# charger.net
KiCad netlist of a schematic drawn in Altium Designer
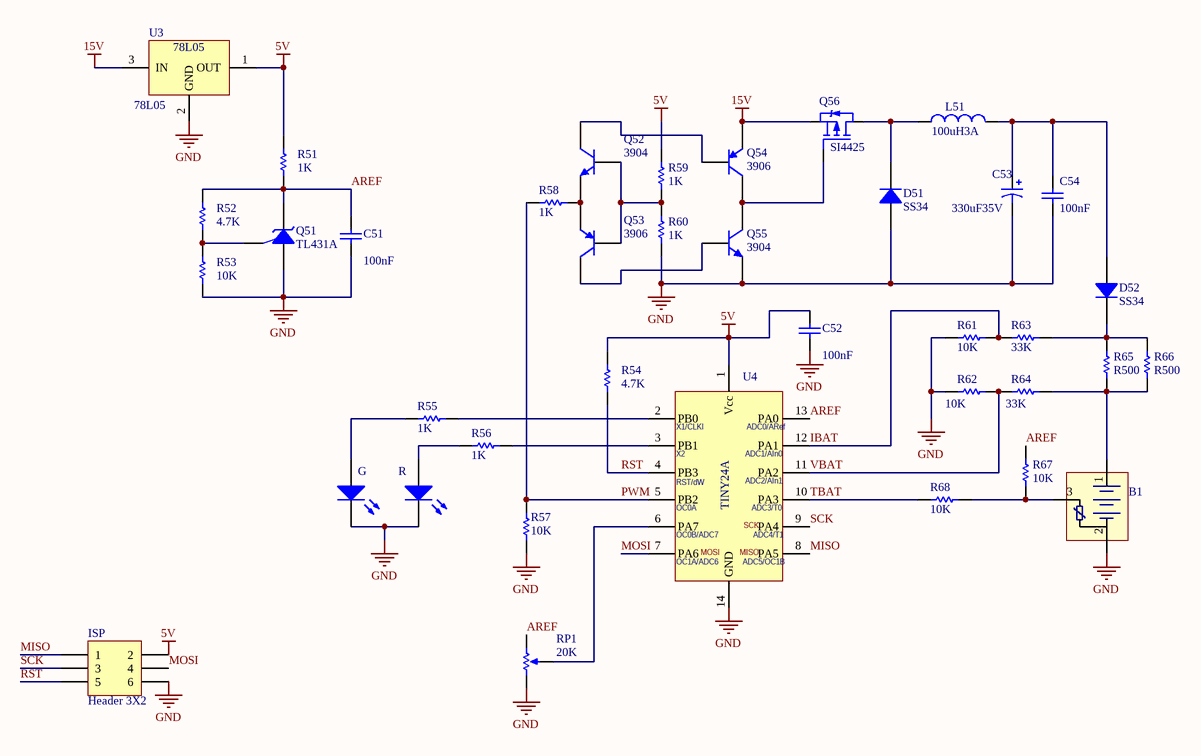
[diagram p0: charger.SchDoc]

(export (version "E")
  (design (tool "Eeschema 10.0.6"))
  (components
    (comp (ref "B1")
      (value "BATT")
      (footprint "BATT")
      (description "电池座")
      (libsource (lib "nizn") (part "BATT"))
    )
    (comp (ref "C51")
      (value "100nF")
      (footprint "CAP0805")
      (description "贴片电容")
      (fields (field (name "Comment") "Cap") (field (name "PUBLISHER") "Altium Limited"))
      (libsource (lib "Miscellaneous Devices") (part "Cap"))
    )
    (comp (ref "C52")
      (value "100nF")
      (footprint "CAP0805")
      (description "贴片电容")
      (fields (field (name "Comment") "Cap") (field (name "PUBLISHER") "Altium Limited"))
      (libsource (lib "Miscellaneous Devices") (part "Cap"))
    )
    (comp (ref "C53")
      (value "330uF35V")
      (footprint "CAP10x16")
      (description "电解电容")
      (fields (field (name "PUBLISHER") "Altium Limited"))
      (libsource (lib "nizn") (part "Cap Pol2"))
    )
    (comp (ref "C54")
      (value "100nF")
      (footprint "CAP0805")
      (description "贴片电容")
      (fields (field (name "Comment") "Cap") (field (name "PUBLISHER") "Altium Limited"))
      (libsource (lib "Miscellaneous Devices") (part "Cap"))
    )
    (comp (ref "D51")
      (value "SS34")
      (footprint "DO214A")
      (description "贴片二极管")
      (fields (field (name "PUBLISHER") "Altium Limited"))
      (libsource (lib "nizn") (part "Diode"))
    )
    (comp (ref "D52")
      (value "SS34")
      (footprint "DO214A")
      (description "贴片二极管")
      (fields (field (name "PUBLISHER") "Altium Limited"))
      (libsource (lib "nizn") (part "Diode"))
    )
    (comp (ref "G")
      (value "高亮翠绿")
      (footprint "LED2G_SLIM")
      (description "贴片二极管 0805")
      (fields (field (name "PUBLISHER") "Altium Limited"))
      (libsource (lib "magcontrol") (part "LED"))
    )
    (comp (ref "ISP")
      (value "Header 3X2")
      (footprint "HDR2X3_EMPTY")
      (description "空")
      (fields (field (name "PUBLISHER") "Altium Limited"))
      (libsource (lib "Miscellaneous Connectors") (part "Header 3X2"))
    )
    (comp (ref "L51")
      (value "100uH3A")
      (footprint "INDUCTOR")
      (description "工字电感")
      (fields (field (name "PUBLISHER") "Altium Limited"))
      (libsource (lib "nizn") (part "Inductor"))
    )
    (comp (ref "Q51")
      (value "TL431A")
      (footprint "SOT23_431")
      (description "基准集成电路")
      (fields (field (name "PUBLISHER") "Altium Limited"))
      (libsource (lib "nizn") (part "TL431"))
    )
    (comp (ref "Q52")
      (value "3904")
      (footprint "SOT23_CBE")
      (description "NPN 三极管")
      (fields (field (name "PUBLISHER") "Altium Limited"))
      (libsource (lib "nizn") (part "NPN"))
    )
    (comp (ref "Q53")
      (value "3906")
      (footprint "SOT23_CBE")
      (description "PNP 三极管")
      (fields (field (name "PUBLISHER") "Altium Limited"))
      (libsource (lib "nizn") (part "PNP"))
    )
    (comp (ref "Q54")
      (value "3906")
      (footprint "SOT23_CBE")
      (description "PNP 三极管")
      (fields (field (name "PUBLISHER") "Altium Limited"))
      (libsource (lib "nizn") (part "PNP"))
    )
    (comp (ref "Q55")
      (value "3904")
      (footprint "SOT23_CBE")
      (description "NPN 三极管")
      (fields (field (name "PUBLISHER") "Altium Limited"))
      (libsource (lib "nizn") (part "NPN"))
    )
    (comp (ref "Q56")
      (value "SI4425")
      (footprint "SO8-MOS")
      (description "低压 PMOS")
      (fields (field (name "PUBLISHER") "Altium Limited"))
      (libsource (lib "nizn") (part "PMOS"))
    )
    (comp (ref "R")
      (value "高亮红")
      (footprint "LED2R_SLIM")
      (description "贴片二极管 0805")
      (fields (field (name "PUBLISHER") "Altium Limited"))
      (libsource (lib "magcontrol") (part "LED"))
    )
    (comp (ref "R51")
      (value "1K")
      (footprint "RES0805")
      (description "贴片电阻")
      (fields (field (name "Comment") "Res1") (field (name "PUBLISHER") "Altium Limited"))
      (libsource (lib "Miscellaneous Devices") (part "Res1"))
    )
    (comp (ref "R52")
      (value "4.7K")
      (footprint "RES0805")
      (description "贴片电阻")
      (fields (field (name "Comment") "Res1") (field (name "PUBLISHER") "Altium Limited"))
      (libsource (lib "Miscellaneous Devices") (part "Res1"))
    )
    (comp (ref "R53")
      (value "10K")
      (footprint "RES0805")
      (description "贴片电阻")
      (fields (field (name "Comment") "Res1") (field (name "PUBLISHER") "Altium Limited"))
      (libsource (lib "Miscellaneous Devices") (part "Res1"))
    )
    (comp (ref "R54")
      (value "4.7K")
      (footprint "RES0805")
      (description "贴片电阻")
      (fields (field (name "Comment") "Res1") (field (name "PUBLISHER") "Altium Limited"))
      (libsource (lib "Miscellaneous Devices") (part "Res1"))
    )
    (comp (ref "R55")
      (value "1K")
      (footprint "RES0805")
      (description "贴片电阻")
      (fields (field (name "Comment") "Res1") (field (name "PUBLISHER") "Altium Limited"))
      (libsource (lib "Miscellaneous Devices") (part "Res1"))
    )
    (comp (ref "R56")
      (value "1K")
      (footprint "RES0805")
      (description "贴片电阻")
      (fields (field (name "Comment") "Res1") (field (name "PUBLISHER") "Altium Limited"))
      (libsource (lib "Miscellaneous Devices") (part "Res1"))
    )
    (comp (ref "R57")
      (value "10K")
      (footprint "RES0805")
      (description "贴片电阻")
      (fields (field (name "Comment") "Res1") (field (name "PUBLISHER") "Altium Limited"))
      (libsource (lib "Miscellaneous Devices") (part "Res1"))
    )
    (comp (ref "R58")
      (value "1K")
      (footprint "RES0805")
      (description "贴片电阻")
      (fields (field (name "Comment") "Res1") (field (name "PUBLISHER") "Altium Limited"))
      (libsource (lib "Miscellaneous Devices") (part "Res1"))
    )
    (comp (ref "R59")
      (value "1K")
      (footprint "RES0805")
      (description "贴片电阻")
      (fields (field (name "Comment") "Res1") (field (name "PUBLISHER") "Altium Limited"))
      (libsource (lib "Miscellaneous Devices") (part "Res1"))
    )
    (comp (ref "R60")
      (value "1K")
      (footprint "RES0805")
      (description "贴片电阻")
      (fields (field (name "Comment") "Res1") (field (name "PUBLISHER") "Altium Limited"))
      (libsource (lib "Miscellaneous Devices") (part "Res1"))
    )
    (comp (ref "R61")
      (value "10K")
      (footprint "RES0805")
      (description "贴片电阻")
      (fields (field (name "Comment") "Res1") (field (name "PUBLISHER") "Altium Limited"))
      (libsource (lib "Miscellaneous Devices") (part "Res1"))
    )
    (comp (ref "R62")
      (value "10K")
      (footprint "RES0805")
      (description "贴片电阻")
      (fields (field (name "Comment") "Res1") (field (name "PUBLISHER") "Altium Limited"))
      (libsource (lib "Miscellaneous Devices") (part "Res1"))
    )
    (comp (ref "R63")
      (value "33K")
      (footprint "RES0805")
      (description "贴片电阻")
      (fields (field (name "Comment") "Res1") (field (name "PUBLISHER") "Altium Limited"))
      (libsource (lib "Miscellaneous Devices") (part "Res1"))
    )
    (comp (ref "R64")
      (value "33K")
      (footprint "RES0805")
      (description "贴片电阻")
      (fields (field (name "Comment") "Res1") (field (name "PUBLISHER") "Altium Limited"))
      (libsource (lib "Miscellaneous Devices") (part "Res1"))
    )
    (comp (ref "R65")
      (value "R500")
      (footprint "RES2512")
      (description "贴片电阻")
      (fields (field (name "Comment") "Res1") (field (name "PUBLISHER") "Altium Limited"))
      (libsource (lib "Miscellaneous Devices") (part "Res1"))
    )
    (comp (ref "R66")
      (value "R500")
      (footprint "RES2512")
      (description "贴片电阻")
      (fields (field (name "Comment") "Res1") (field (name "PUBLISHER") "Altium Limited"))
      (libsource (lib "Miscellaneous Devices") (part "Res1"))
    )
    (comp (ref "R67")
      (value "10K")
      (footprint "RES0805")
      (description "贴片电阻")
      (fields (field (name "Comment") "Res1") (field (name "PUBLISHER") "Altium Limited"))
      (libsource (lib "Miscellaneous Devices") (part "Res1"))
    )
    (comp (ref "R68")
      (value "10K")
      (footprint "RES0805")
      (description "贴片电阻")
      (fields (field (name "Comment") "Res1") (field (name "PUBLISHER") "Altium Limited"))
      (libsource (lib "Miscellaneous Devices") (part "Res1"))
    )
    (comp (ref "RP1")
      (value "20K")
      (footprint "POT3x3")
      (description "贴片电位器")
      (fields (field (name "Comment") "RPot") (field (name "PUBLISHER") "Altium Limited"))
      (libsource (lib "Miscellaneous Devices") (part "RPot"))
    )
    (comp (ref "U3")
      (value "78L05")
      (footprint "SOT89_VREG")
      (description "三端稳压贴片")
      (fields (field (name "PUBLISHER") "Altium Limited"))
      (libsource (lib "magcontrol") (part "78L05"))
    )
    (comp (ref "U4")
      (value "TINY24A")
      (footprint "SO14")
      (description "集成电路")
      (libsource (lib "nizn") (part "TINY13A"))
    )
  )
  (nets
    (net (code "1") (name "/AREF") (class "Default")
      (node (ref "C51") (pin "2") (pinfunction "2_2") (pintype "passive"))
      (node (ref "Q51") (pin "3") (pinfunction "C_3") (pintype "passive"))
      (node (ref "R51") (pin "1") (pinfunction "1_1") (pintype "passive"))
      (node (ref "R52") (pin "2") (pinfunction "2_2") (pintype "passive"))
      (node (ref "R67") (pin "2") (pinfunction "2_2") (pintype "passive"))
      (node (ref "RP1") (pin "2") (pinfunction "BOT_2") (pintype "passive"))
      (node (ref "U4") (pin "13") (pinfunction "PA0_13") (pintype "power_in"))
    )
    (net (code "2") (name "/IBAT") (class "Default")
      (node (ref "R61") (pin "1") (pinfunction "1_1") (pintype "passive"))
      (node (ref "R63") (pin "2") (pinfunction "2_2") (pintype "passive"))
      (node (ref "U4") (pin "12") (pinfunction "PA1_12") (pintype "power_in"))
    )
    (net (code "3") (name "/MISO") (class "Default")
      (node (ref "ISP") (pin "1") (pinfunction "1_1") (pintype "passive"))
      (node (ref "U4") (pin "8") (pinfunction "PA5_8") (pintype "power_in"))
    )
    (net (code "4") (name "/MOSI") (class "Default")
      (node (ref "ISP") (pin "4") (pinfunction "4_4") (pintype "passive"))
      (node (ref "U4") (pin "7") (pinfunction "PA6_7") (pintype "power_in"))
    )
    (net (code "5") (name "/PWM") (class "Default")
      (node (ref "R57") (pin "1") (pinfunction "1_1") (pintype "passive"))
      (node (ref "R58") (pin "2") (pinfunction "2_2") (pintype "passive"))
      (node (ref "U4") (pin "5") (pinfunction "PB2_5") (pintype "power_in"))
    )
    (net (code "6") (name "/RST") (class "Default")
      (node (ref "ISP") (pin "5") (pinfunction "5_5") (pintype "passive"))
      (node (ref "R54") (pin "1") (pinfunction "1_1") (pintype "passive"))
      (node (ref "U4") (pin "4") (pinfunction "PB3_4") (pintype "power_in"))
    )
    (net (code "7") (name "/SCK") (class "Default")
      (node (ref "ISP") (pin "3") (pinfunction "3_3") (pintype "passive"))
      (node (ref "U4") (pin "9") (pinfunction "PA4_9") (pintype "power_in"))
    )
    (net (code "8") (name "/TBAT") (class "Default")
      (node (ref "R68") (pin "2") (pinfunction "2_2") (pintype "passive"))
      (node (ref "U4") (pin "10") (pinfunction "PA3_10") (pintype "power_in"))
    )
    (net (code "9") (name "/VBAT") (class "Default")
      (node (ref "R62") (pin "1") (pinfunction "1_1") (pintype "passive"))
      (node (ref "R64") (pin "2") (pinfunction "2_2") (pintype "passive"))
      (node (ref "U4") (pin "11") (pinfunction "PA2_11") (pintype "power_in"))
    )
    (net (code "10") (name "5V") (class "Default")
      (node (ref "C52") (pin "2") (pinfunction "2_2") (pintype "passive"))
      (node (ref "ISP") (pin "2") (pinfunction "2_2") (pintype "passive"))
      (node (ref "R51") (pin "2") (pinfunction "2_2") (pintype "passive"))
      (node (ref "R54") (pin "2") (pinfunction "2_2") (pintype "passive"))
      (node (ref "R59") (pin "2") (pinfunction "2_2") (pintype "passive"))
      (node (ref "U3") (pin "1") (pinfunction "OUT_1") (pintype "power_in"))
      (node (ref "U4") (pin "1") (pinfunction "Vcc_1") (pintype "power_in"))
    )
    (net (code "11") (name "15V") (class "Default")
      (node (ref "Q54") (pin "E") (pinfunction "E_E") (pintype "passive"))
      (node (ref "Q56") (pin "S") (pinfunction "S_S") (pintype "passive"))
      (node (ref "U3") (pin "3") (pinfunction "IN_3") (pintype "power_in"))
    )
    (net (code "12") (name "GND") (class "Default")
      (node (ref "B1") (pin "2") (pinfunction "B-_2") (pintype "power_in"))
      (node (ref "C51") (pin "1") (pinfunction "1_1") (pintype "passive"))
      (node (ref "C52") (pin "1") (pinfunction "1_1") (pintype "passive"))
      (node (ref "C53") (pin "2") (pinfunction "2_2") (pintype "passive"))
      (node (ref "C54") (pin "1") (pinfunction "1_1") (pintype "passive"))
      (node (ref "D51") (pin "1") (pinfunction "A_1") (pintype "passive"))
      (node (ref "G") (pin "2") (pinfunction "K_2") (pintype "passive"))
      (node (ref "ISP") (pin "6") (pinfunction "6_6") (pintype "passive"))
      (node (ref "Q51") (pin "2") (pinfunction "A_2") (pintype "passive"))
      (node (ref "Q55") (pin "E") (pinfunction "E_E") (pintype "passive"))
      (node (ref "R") (pin "2") (pinfunction "K_2") (pintype "passive"))
      (node (ref "R53") (pin "1") (pinfunction "1_1") (pintype "passive"))
      (node (ref "R57") (pin "2") (pinfunction "2_2") (pintype "passive"))
      (node (ref "R60") (pin "1") (pinfunction "1_1") (pintype "passive"))
      (node (ref "R61") (pin "2") (pinfunction "2_2") (pintype "passive"))
      (node (ref "R62") (pin "2") (pinfunction "2_2") (pintype "passive"))
      (node (ref "RP1") (pin "1") (pinfunction "TOP_1") (pintype "passive"))
      (node (ref "U3") (pin "2") (pinfunction "GND_2") (pintype "power_in"))
      (node (ref "U4") (pin "14") (pinfunction "GND_14") (pintype "power_in"))
    )
    (net (code "13") (name "Net-(B1-B+)") (class "Default")
      (node (ref "B1") (pin "1") (pinfunction "B+_1") (pintype "power_in"))
      (node (ref "R64") (pin "1") (pinfunction "1_1") (pintype "passive"))
      (node (ref "R65") (pin "1") (pinfunction "1_1") (pintype "passive"))
      (node (ref "R66") (pin "1") (pinfunction "1_1") (pintype "passive"))
    )
    (net (code "14") (name "Net-(B1-T)") (class "Default")
      (node (ref "B1") (pin "3") (pinfunction "T_3") (pintype "power_in"))
      (node (ref "R67") (pin "1") (pinfunction "1_1") (pintype "passive"))
      (node (ref "R68") (pin "1") (pinfunction "1_1") (pintype "passive"))
    )
    (net (code "15") (name "Net-(D51-K)") (class "Default")
      (node (ref "D51") (pin "2") (pinfunction "K_2") (pintype "passive"))
      (node (ref "L51") (pin "1") (pinfunction "1_1") (pintype "passive"))
      (node (ref "Q56") (pin "D") (pinfunction "D_D") (pintype "passive"))
    )
    (net (code "16") (name "Net-(D52-A)") (class "Default")
      (node (ref "C53") (pin "1") (pinfunction "1_1") (pintype "passive"))
      (node (ref "C54") (pin "2") (pinfunction "2_2") (pintype "passive"))
      (node (ref "D52") (pin "1") (pinfunction "A_1") (pintype "passive"))
      (node (ref "L51") (pin "2") (pinfunction "2_2") (pintype "passive"))
    )
    (net (code "17") (name "Net-(D52-K)") (class "Default")
      (node (ref "D52") (pin "2") (pinfunction "K_2") (pintype "passive"))
      (node (ref "R63") (pin "1") (pinfunction "1_1") (pintype "passive"))
      (node (ref "R65") (pin "2") (pinfunction "2_2") (pintype "passive"))
      (node (ref "R66") (pin "2") (pinfunction "2_2") (pintype "passive"))
    )
    (net (code "18") (name "Net-(G-A)") (class "Default")
      (node (ref "G") (pin "1") (pinfunction "A_1") (pintype "passive"))
      (node (ref "R55") (pin "2") (pinfunction "2_2") (pintype "passive"))
    )
    (net (code "19") (name "Net-(Q51-R)") (class "Default")
      (node (ref "Q51") (pin "1") (pinfunction "R_1") (pintype "passive"))
      (node (ref "R52") (pin "1") (pinfunction "1_1") (pintype "passive"))
      (node (ref "R53") (pin "2") (pinfunction "2_2") (pintype "passive"))
    )
    (net (code "20") (name "Net-(Q52-PadB)") (class "Default")
      (node (ref "Q52") (pin "B") (pinfunction "B_B") (pintype "passive"))
      (node (ref "Q53") (pin "B") (pinfunction "B_B") (pintype "passive"))
      (node (ref "R59") (pin "1") (pinfunction "1_1") (pintype "passive"))
      (node (ref "R60") (pin "2") (pinfunction "2_2") (pintype "passive"))
    )
    (net (code "21") (name "Net-(Q52-PadC)") (class "Default")
      (node (ref "Q52") (pin "C") (pinfunction "C_C") (pintype "passive"))
      (node (ref "Q54") (pin "B") (pinfunction "B_B") (pintype "passive"))
    )
    (net (code "22") (name "Net-(Q52-PadE)") (class "Default")
      (node (ref "Q52") (pin "E") (pinfunction "E_E") (pintype "passive"))
      (node (ref "Q53") (pin "E") (pinfunction "E_E") (pintype "passive"))
      (node (ref "R58") (pin "1") (pinfunction "1_1") (pintype "passive"))
    )
    (net (code "23") (name "Net-(Q53-PadC)") (class "Default")
      (node (ref "Q53") (pin "C") (pinfunction "C_C") (pintype "passive"))
      (node (ref "Q55") (pin "B") (pinfunction "B_B") (pintype "passive"))
    )
    (net (code "24") (name "Net-(Q54-PadC)") (class "Default")
      (node (ref "Q54") (pin "C") (pinfunction "C_C") (pintype "passive"))
      (node (ref "Q55") (pin "C") (pinfunction "C_C") (pintype "passive"))
      (node (ref "Q56") (pin "G") (pinfunction "G_G") (pintype "passive"))
    )
    (net (code "25") (name "Net-(R-A)") (class "Default")
      (node (ref "R") (pin "1") (pinfunction "A_1") (pintype "passive"))
      (node (ref "R56") (pin "2") (pinfunction "2_2") (pintype "passive"))
    )
    (net (code "26") (name "Net-(RP1-TAP)") (class "Default")
      (node (ref "RP1") (pin "3") (pinfunction "TAP_3") (pintype "passive"))
      (node (ref "U4") (pin "6") (pinfunction "PA7_6") (pintype "power_in"))
    )
    (net (code "27") (name "Net-(U4-PB0)") (class "Default")
      (node (ref "R55") (pin "1") (pinfunction "1_1") (pintype "passive"))
      (node (ref "U4") (pin "2") (pinfunction "PB0_2") (pintype "power_in"))
    )
    (net (code "28") (name "Net-(U4-PB1)") (class "Default")
      (node (ref "R56") (pin "1") (pinfunction "1_1") (pintype "passive"))
      (node (ref "U4") (pin "3") (pinfunction "PB1_3") (pintype "power_in"))
    )
  )
)
